# activity_monitor_v1_2.net
KiCad netlist of a schematic drawn in EAGLE
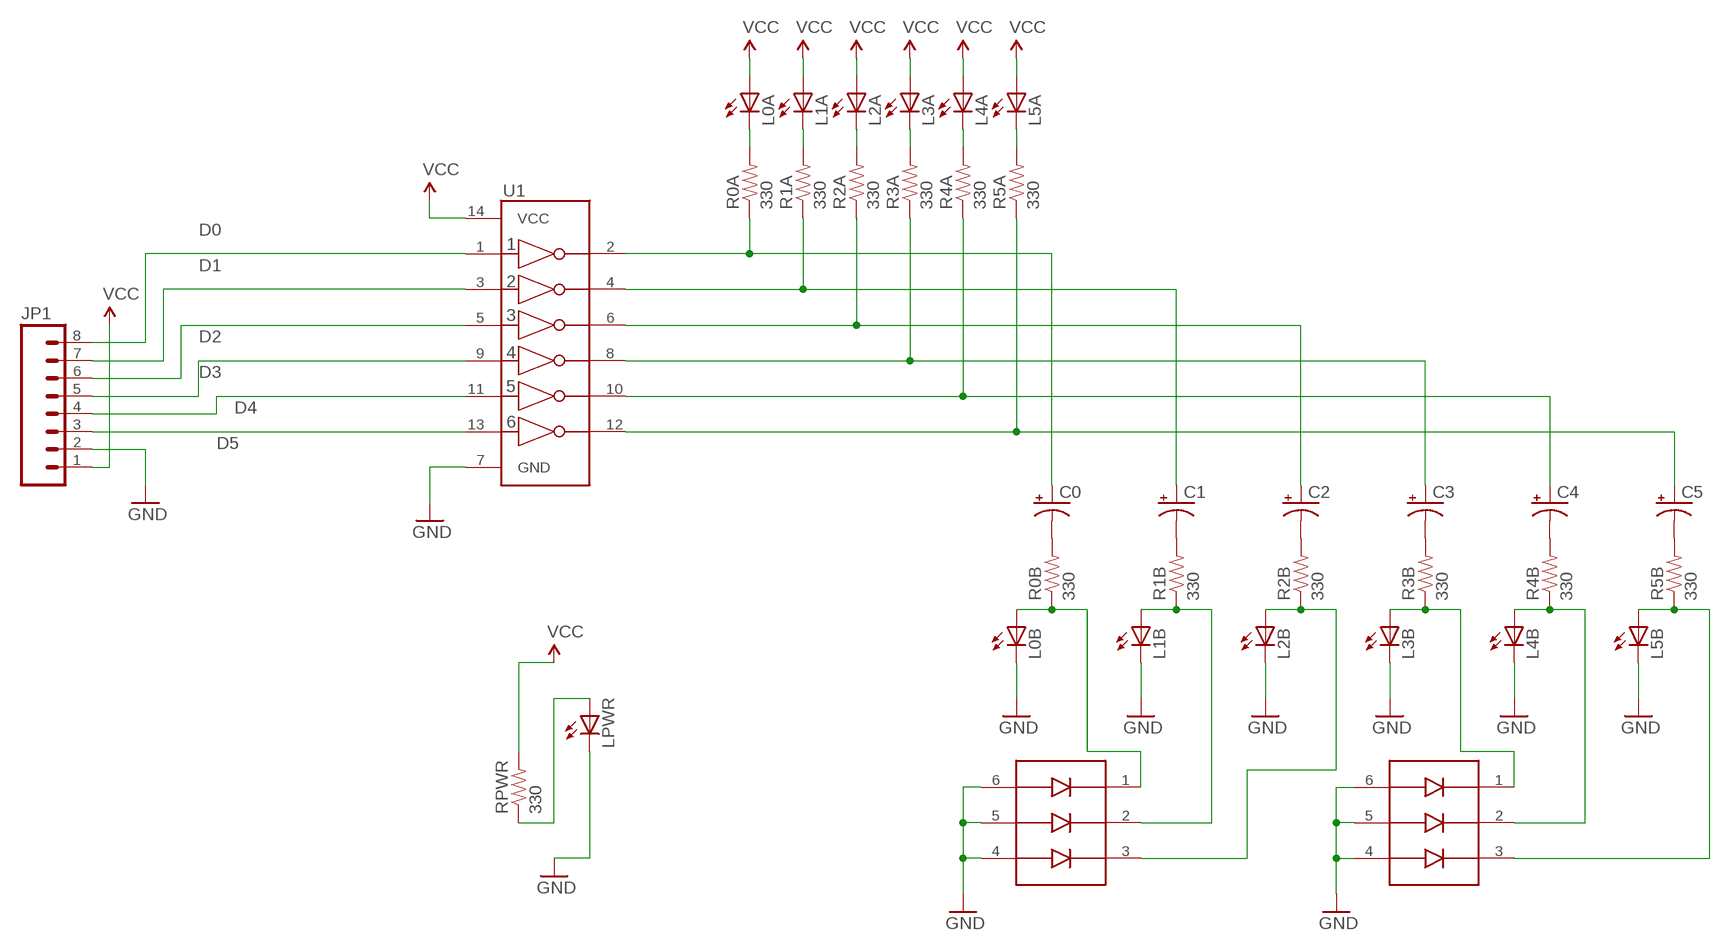
[diagram p0: schematic, sheet 1]

(export (version "E")
  (design (tool "Eeschema 10.0.6"))
  (components
    (comp (ref "C0")
      (value "10UF-TANT")
      (footprint "eagle-import:EIA3216")
      (libsource (lib "eagle-import") (part "10UF-TANT"))
    )
    (comp (ref "C1")
      (value "10UF-TANT")
      (footprint "eagle-import:EIA3216")
      (libsource (lib "eagle-import") (part "10UF-TANT"))
    )
    (comp (ref "C2")
      (value "10UF-TANT")
      (footprint "eagle-import:EIA3216")
      (libsource (lib "eagle-import") (part "10UF-TANT"))
    )
    (comp (ref "C3")
      (value "10UF-TANT")
      (footprint "eagle-import:EIA3216")
      (libsource (lib "eagle-import") (part "10UF-TANT"))
    )
    (comp (ref "C4")
      (value "10UF-TANT")
      (footprint "eagle-import:EIA3216")
      (libsource (lib "eagle-import") (part "10UF-TANT"))
    )
    (comp (ref "C5")
      (value "10UF-TANT")
      (footprint "eagle-import:EIA3216")
      (libsource (lib "eagle-import") (part "10UF-TANT"))
    )
    (comp (ref "JP1")
      (value "M081X08")
      (footprint "eagle-import:1X08")
      (libsource (lib "eagle-import") (part "M081X08"))
    )
    (comp (ref "L0A")
      (value "LED0603")
      (footprint "eagle-import:LED-0603")
      (libsource (lib "eagle-import") (part "LED0603"))
    )
    (comp (ref "L0B")
      (value "LED0603")
      (footprint "eagle-import:LED-0603")
      (libsource (lib "eagle-import") (part "LED0603"))
    )
    (comp (ref "L1A")
      (value "LED0603")
      (footprint "eagle-import:LED-0603")
      (libsource (lib "eagle-import") (part "LED0603"))
    )
    (comp (ref "L1B")
      (value "LED0603")
      (footprint "eagle-import:LED-0603")
      (libsource (lib "eagle-import") (part "LED0603"))
    )
    (comp (ref "L2A")
      (value "LED0603")
      (footprint "eagle-import:LED-0603")
      (libsource (lib "eagle-import") (part "LED0603"))
    )
    (comp (ref "L2B")
      (value "LED0603")
      (footprint "eagle-import:LED-0603")
      (libsource (lib "eagle-import") (part "LED0603"))
    )
    (comp (ref "L3A")
      (value "LED0603")
      (footprint "eagle-import:LED-0603")
      (libsource (lib "eagle-import") (part "LED0603"))
    )
    (comp (ref "L3B")
      (value "LED0603")
      (footprint "eagle-import:LED-0603")
      (libsource (lib "eagle-import") (part "LED0603"))
    )
    (comp (ref "L4A")
      (value "LED0603")
      (footprint "eagle-import:LED-0603")
      (libsource (lib "eagle-import") (part "LED0603"))
    )
    (comp (ref "L4B")
      (value "LED0603")
      (footprint "eagle-import:LED-0603")
      (libsource (lib "eagle-import") (part "LED0603"))
    )
    (comp (ref "L5A")
      (value "LED0603")
      (footprint "eagle-import:LED-0603")
      (libsource (lib "eagle-import") (part "LED0603"))
    )
    (comp (ref "L5B")
      (value "LED0603")
      (footprint "eagle-import:LED-0603")
      (libsource (lib "eagle-import") (part "LED0603"))
    )
    (comp (ref "LPWR")
      (value "LED0603")
      (footprint "eagle-import:LED-0603")
      (libsource (lib "eagle-import") (part "LED0603"))
    )
    (comp (ref "R0A")
      (value "330")
      (footprint "eagle-import:0603-RES")
      (libsource (lib "eagle-import") (part "RESISTOR0603-RES"))
    )
    (comp (ref "R0B")
      (value "330")
      (footprint "eagle-import:0603-RES")
      (libsource (lib "eagle-import") (part "RESISTOR0603-RES"))
    )
    (comp (ref "R1A")
      (value "330")
      (footprint "eagle-import:0603-RES")
      (libsource (lib "eagle-import") (part "RESISTOR0603-RES"))
    )
    (comp (ref "R1B")
      (value "330")
      (footprint "eagle-import:0603-RES")
      (libsource (lib "eagle-import") (part "RESISTOR0603-RES"))
    )
    (comp (ref "R2A")
      (value "330")
      (footprint "eagle-import:0603-RES")
      (libsource (lib "eagle-import") (part "RESISTOR0603-RES"))
    )
    (comp (ref "R2B")
      (value "330")
      (footprint "eagle-import:0603-RES")
      (libsource (lib "eagle-import") (part "RESISTOR0603-RES"))
    )
    (comp (ref "R3A")
      (value "330")
      (footprint "eagle-import:0603-RES")
      (libsource (lib "eagle-import") (part "RESISTOR0603-RES"))
    )
    (comp (ref "R3B")
      (value "330")
      (footprint "eagle-import:0603-RES")
      (libsource (lib "eagle-import") (part "RESISTOR0603-RES"))
    )
    (comp (ref "R4A")
      (value "330")
      (footprint "eagle-import:0603-RES")
      (libsource (lib "eagle-import") (part "RESISTOR0603-RES"))
    )
    (comp (ref "R4B")
      (value "330")
      (footprint "eagle-import:0603-RES")
      (libsource (lib "eagle-import") (part "RESISTOR0603-RES"))
    )
    (comp (ref "R5A")
      (value "330")
      (footprint "eagle-import:0603-RES")
      (libsource (lib "eagle-import") (part "RESISTOR0603-RES"))
    )
    (comp (ref "R5B")
      (value "330")
      (footprint "eagle-import:0603-RES")
      (libsource (lib "eagle-import") (part "RESISTOR0603-RES"))
    )
    (comp (ref "RPWR")
      (value "330")
      (footprint "eagle-import:0603-RES")
      (libsource (lib "eagle-import") (part "RESISTOR0603-RES"))
    )
    (comp (ref "U$1")
      (value "SD103ATW-7-F")
      (footprint "eagle-import:SOT363")
      (libsource (lib "eagle-import") (part "SD103ATW-7-F"))
    )
    (comp (ref "U$2")
      (value "SD103ATW-7-F")
      (footprint "eagle-import:SOT363")
      (libsource (lib "eagle-import") (part "SD103ATW-7-F"))
    )
    (comp (ref "U1")
      (value "74HC04_HEX_INVERTERTSSOP14")
      (footprint "eagle-import:TSSOP14")
      (libsource (lib "eagle-import") (part "74HC04_HEX_INVERTERTSSOP14"))
    )
  )
  (nets
    (net (code "1") (name "/D0") (class "Default")
      (node (ref "JP1") (pin "8") (pinfunction "8_8") (pintype "passive"))
      (node (ref "U1") (pin "1") (pinfunction "1A_1") (pintype "input"))
    )
    (net (code "2") (name "/D1") (class "Default")
      (node (ref "JP1") (pin "7") (pinfunction "7_7") (pintype "passive"))
      (node (ref "U1") (pin "3") (pinfunction "2A_3") (pintype "input"))
    )
    (net (code "3") (name "/D2") (class "Default")
      (node (ref "JP1") (pin "6") (pinfunction "6_6") (pintype "passive"))
      (node (ref "U1") (pin "5") (pinfunction "3A_5") (pintype "input"))
    )
    (net (code "4") (name "/D3") (class "Default")
      (node (ref "JP1") (pin "5") (pinfunction "5_5") (pintype "passive"))
      (node (ref "U1") (pin "9") (pinfunction "4A_9") (pintype "input"))
    )
    (net (code "5") (name "/D4") (class "Default")
      (node (ref "JP1") (pin "4") (pinfunction "4_4") (pintype "passive"))
      (node (ref "U1") (pin "11") (pinfunction "5A_11") (pintype "input"))
    )
    (net (code "6") (name "/D5") (class "Default")
      (node (ref "JP1") (pin "3") (pinfunction "3_3") (pintype "passive"))
      (node (ref "U1") (pin "13") (pinfunction "6A_13") (pintype "input"))
    )
    (net (code "7") (name "GND") (class "Default")
      (node (ref "JP1") (pin "2") (pinfunction "2_2") (pintype "passive"))
      (node (ref "L0B") (pin "C") (pinfunction "C_C") (pintype "passive"))
      (node (ref "L1B") (pin "C") (pinfunction "C_C") (pintype "passive"))
      (node (ref "L2B") (pin "C") (pinfunction "C_C") (pintype "passive"))
      (node (ref "L3B") (pin "C") (pinfunction "C_C") (pintype "passive"))
      (node (ref "L4B") (pin "C") (pinfunction "C_C") (pintype "passive"))
      (node (ref "L5B") (pin "C") (pinfunction "C_C") (pintype "passive"))
      (node (ref "LPWR") (pin "C") (pinfunction "C_C") (pintype "passive"))
      (node (ref "U$1") (pin "4") (pinfunction "I3_4") (pintype "bidirectional"))
      (node (ref "U$1") (pin "5") (pinfunction "I2_5") (pintype "bidirectional"))
      (node (ref "U$1") (pin "6") (pinfunction "I1_6") (pintype "bidirectional"))
      (node (ref "U$2") (pin "4") (pinfunction "I3_4") (pintype "bidirectional"))
      (node (ref "U$2") (pin "5") (pinfunction "I2_5") (pintype "bidirectional"))
      (node (ref "U$2") (pin "6") (pinfunction "I1_6") (pintype "bidirectional"))
      (node (ref "U1") (pin "7") (pinfunction "GND_7") (pintype "power_in"))
    )
    (net (code "8") (name "Net-(C0-+)") (class "Default")
      (node (ref "C0") (pin "A") (pinfunction "+_A") (pintype "passive"))
      (node (ref "R0A") (pin "1") (pinfunction "1_1") (pintype "passive"))
      (node (ref "U1") (pin "2") (pinfunction "1Y_2") (pintype "output"))
    )
    (net (code "9") (name "Net-(C0--)") (class "Default")
      (node (ref "C0") (pin "C") (pinfunction "-_C") (pintype "passive"))
      (node (ref "R0B") (pin "2") (pinfunction "2_2") (pintype "passive"))
    )
    (net (code "10") (name "Net-(C1-+)") (class "Default")
      (node (ref "C1") (pin "A") (pinfunction "+_A") (pintype "passive"))
      (node (ref "R1A") (pin "1") (pinfunction "1_1") (pintype "passive"))
      (node (ref "U1") (pin "4") (pinfunction "2Y_4") (pintype "output"))
    )
    (net (code "11") (name "Net-(C1--)") (class "Default")
      (node (ref "C1") (pin "C") (pinfunction "-_C") (pintype "passive"))
      (node (ref "R1B") (pin "2") (pinfunction "2_2") (pintype "passive"))
    )
    (net (code "12") (name "Net-(C2-+)") (class "Default")
      (node (ref "C2") (pin "A") (pinfunction "+_A") (pintype "passive"))
      (node (ref "R2A") (pin "1") (pinfunction "1_1") (pintype "passive"))
      (node (ref "U1") (pin "6") (pinfunction "3Y_6") (pintype "output"))
    )
    (net (code "13") (name "Net-(C2--)") (class "Default")
      (node (ref "C2") (pin "C") (pinfunction "-_C") (pintype "passive"))
      (node (ref "R2B") (pin "2") (pinfunction "2_2") (pintype "passive"))
    )
    (net (code "14") (name "Net-(C3-+)") (class "Default")
      (node (ref "C3") (pin "A") (pinfunction "+_A") (pintype "passive"))
      (node (ref "R3A") (pin "1") (pinfunction "1_1") (pintype "passive"))
      (node (ref "U1") (pin "8") (pinfunction "4Y_8") (pintype "output"))
    )
    (net (code "15") (name "Net-(C3--)") (class "Default")
      (node (ref "C3") (pin "C") (pinfunction "-_C") (pintype "passive"))
      (node (ref "R3B") (pin "2") (pinfunction "2_2") (pintype "passive"))
    )
    (net (code "16") (name "Net-(C4-+)") (class "Default")
      (node (ref "C4") (pin "A") (pinfunction "+_A") (pintype "passive"))
      (node (ref "R4A") (pin "1") (pinfunction "1_1") (pintype "passive"))
      (node (ref "U1") (pin "10") (pinfunction "5Y_10") (pintype "output"))
    )
    (net (code "17") (name "Net-(C4--)") (class "Default")
      (node (ref "C4") (pin "C") (pinfunction "-_C") (pintype "passive"))
      (node (ref "R4B") (pin "2") (pinfunction "2_2") (pintype "passive"))
    )
    (net (code "18") (name "Net-(C5-+)") (class "Default")
      (node (ref "C5") (pin "A") (pinfunction "+_A") (pintype "passive"))
      (node (ref "R5A") (pin "1") (pinfunction "1_1") (pintype "passive"))
      (node (ref "U1") (pin "12") (pinfunction "6Y_12") (pintype "output"))
    )
    (net (code "19") (name "Net-(C5--)") (class "Default")
      (node (ref "C5") (pin "C") (pinfunction "-_C") (pintype "passive"))
      (node (ref "R5B") (pin "2") (pinfunction "2_2") (pintype "passive"))
    )
    (net (code "20") (name "Net-(L0A-PadC)") (class "Default")
      (node (ref "L0A") (pin "C") (pinfunction "C_C") (pintype "passive"))
      (node (ref "R0A") (pin "2") (pinfunction "2_2") (pintype "passive"))
    )
    (net (code "21") (name "Net-(L1A-PadC)") (class "Default")
      (node (ref "L1A") (pin "C") (pinfunction "C_C") (pintype "passive"))
      (node (ref "R1A") (pin "2") (pinfunction "2_2") (pintype "passive"))
    )
    (net (code "22") (name "Net-(L2A-PadC)") (class "Default")
      (node (ref "L2A") (pin "C") (pinfunction "C_C") (pintype "passive"))
      (node (ref "R2A") (pin "2") (pinfunction "2_2") (pintype "passive"))
    )
    (net (code "23") (name "Net-(L3A-PadC)") (class "Default")
      (node (ref "L3A") (pin "C") (pinfunction "C_C") (pintype "passive"))
      (node (ref "R3A") (pin "2") (pinfunction "2_2") (pintype "passive"))
    )
    (net (code "24") (name "Net-(L4A-PadC)") (class "Default")
      (node (ref "L4A") (pin "C") (pinfunction "C_C") (pintype "passive"))
      (node (ref "R4A") (pin "2") (pinfunction "2_2") (pintype "passive"))
    )
    (net (code "25") (name "Net-(L5A-PadC)") (class "Default")
      (node (ref "L5A") (pin "C") (pinfunction "C_C") (pintype "passive"))
      (node (ref "R5A") (pin "2") (pinfunction "2_2") (pintype "passive"))
    )
    (net (code "26") (name "Net-(LPWR-PadA)") (class "Default")
      (node (ref "LPWR") (pin "A") (pinfunction "A_A") (pintype "passive"))
      (node (ref "RPWR") (pin "1") (pinfunction "1_1") (pintype "passive"))
    )
    (net (code "27") (name "Net-(U$1-O1)") (class "Default")
      (node (ref "L0B") (pin "A") (pinfunction "A_A") (pintype "passive"))
      (node (ref "R0B") (pin "1") (pinfunction "1_1") (pintype "passive"))
      (node (ref "U$1") (pin "1") (pinfunction "O1_1") (pintype "bidirectional"))
    )
    (net (code "28") (name "Net-(U$1-O2)") (class "Default")
      (node (ref "L1B") (pin "A") (pinfunction "A_A") (pintype "passive"))
      (node (ref "R1B") (pin "1") (pinfunction "1_1") (pintype "passive"))
      (node (ref "U$1") (pin "2") (pinfunction "O2_2") (pintype "bidirectional"))
    )
    (net (code "29") (name "Net-(U$1-O3)") (class "Default")
      (node (ref "L2B") (pin "A") (pinfunction "A_A") (pintype "passive"))
      (node (ref "R2B") (pin "1") (pinfunction "1_1") (pintype "passive"))
      (node (ref "U$1") (pin "3") (pinfunction "O3_3") (pintype "bidirectional"))
    )
    (net (code "30") (name "Net-(U$2-O1)") (class "Default")
      (node (ref "L3B") (pin "A") (pinfunction "A_A") (pintype "passive"))
      (node (ref "R3B") (pin "1") (pinfunction "1_1") (pintype "passive"))
      (node (ref "U$2") (pin "1") (pinfunction "O1_1") (pintype "bidirectional"))
    )
    (net (code "31") (name "Net-(U$2-O2)") (class "Default")
      (node (ref "L4B") (pin "A") (pinfunction "A_A") (pintype "passive"))
      (node (ref "R4B") (pin "1") (pinfunction "1_1") (pintype "passive"))
      (node (ref "U$2") (pin "2") (pinfunction "O2_2") (pintype "bidirectional"))
    )
    (net (code "32") (name "Net-(U$2-O3)") (class "Default")
      (node (ref "L5B") (pin "A") (pinfunction "A_A") (pintype "passive"))
      (node (ref "R5B") (pin "1") (pinfunction "1_1") (pintype "passive"))
      (node (ref "U$2") (pin "3") (pinfunction "O3_3") (pintype "bidirectional"))
    )
    (net (code "33") (name "VCC") (class "Default")
      (node (ref "JP1") (pin "1") (pinfunction "1_1") (pintype "passive"))
      (node (ref "L0A") (pin "A") (pinfunction "A_A") (pintype "passive"))
      (node (ref "L1A") (pin "A") (pinfunction "A_A") (pintype "passive"))
      (node (ref "L2A") (pin "A") (pinfunction "A_A") (pintype "passive"))
      (node (ref "L3A") (pin "A") (pinfunction "A_A") (pintype "passive"))
      (node (ref "L4A") (pin "A") (pinfunction "A_A") (pintype "passive"))
      (node (ref "L5A") (pin "A") (pinfunction "A_A") (pintype "passive"))
      (node (ref "RPWR") (pin "2") (pinfunction "2_2") (pintype "passive"))
      (node (ref "U1") (pin "14") (pinfunction "VCC_14") (pintype "power_in"))
    )
  )
)
